# GritMaker.net
KiCad netlist of a schematic drawn in EasyEDA Pro
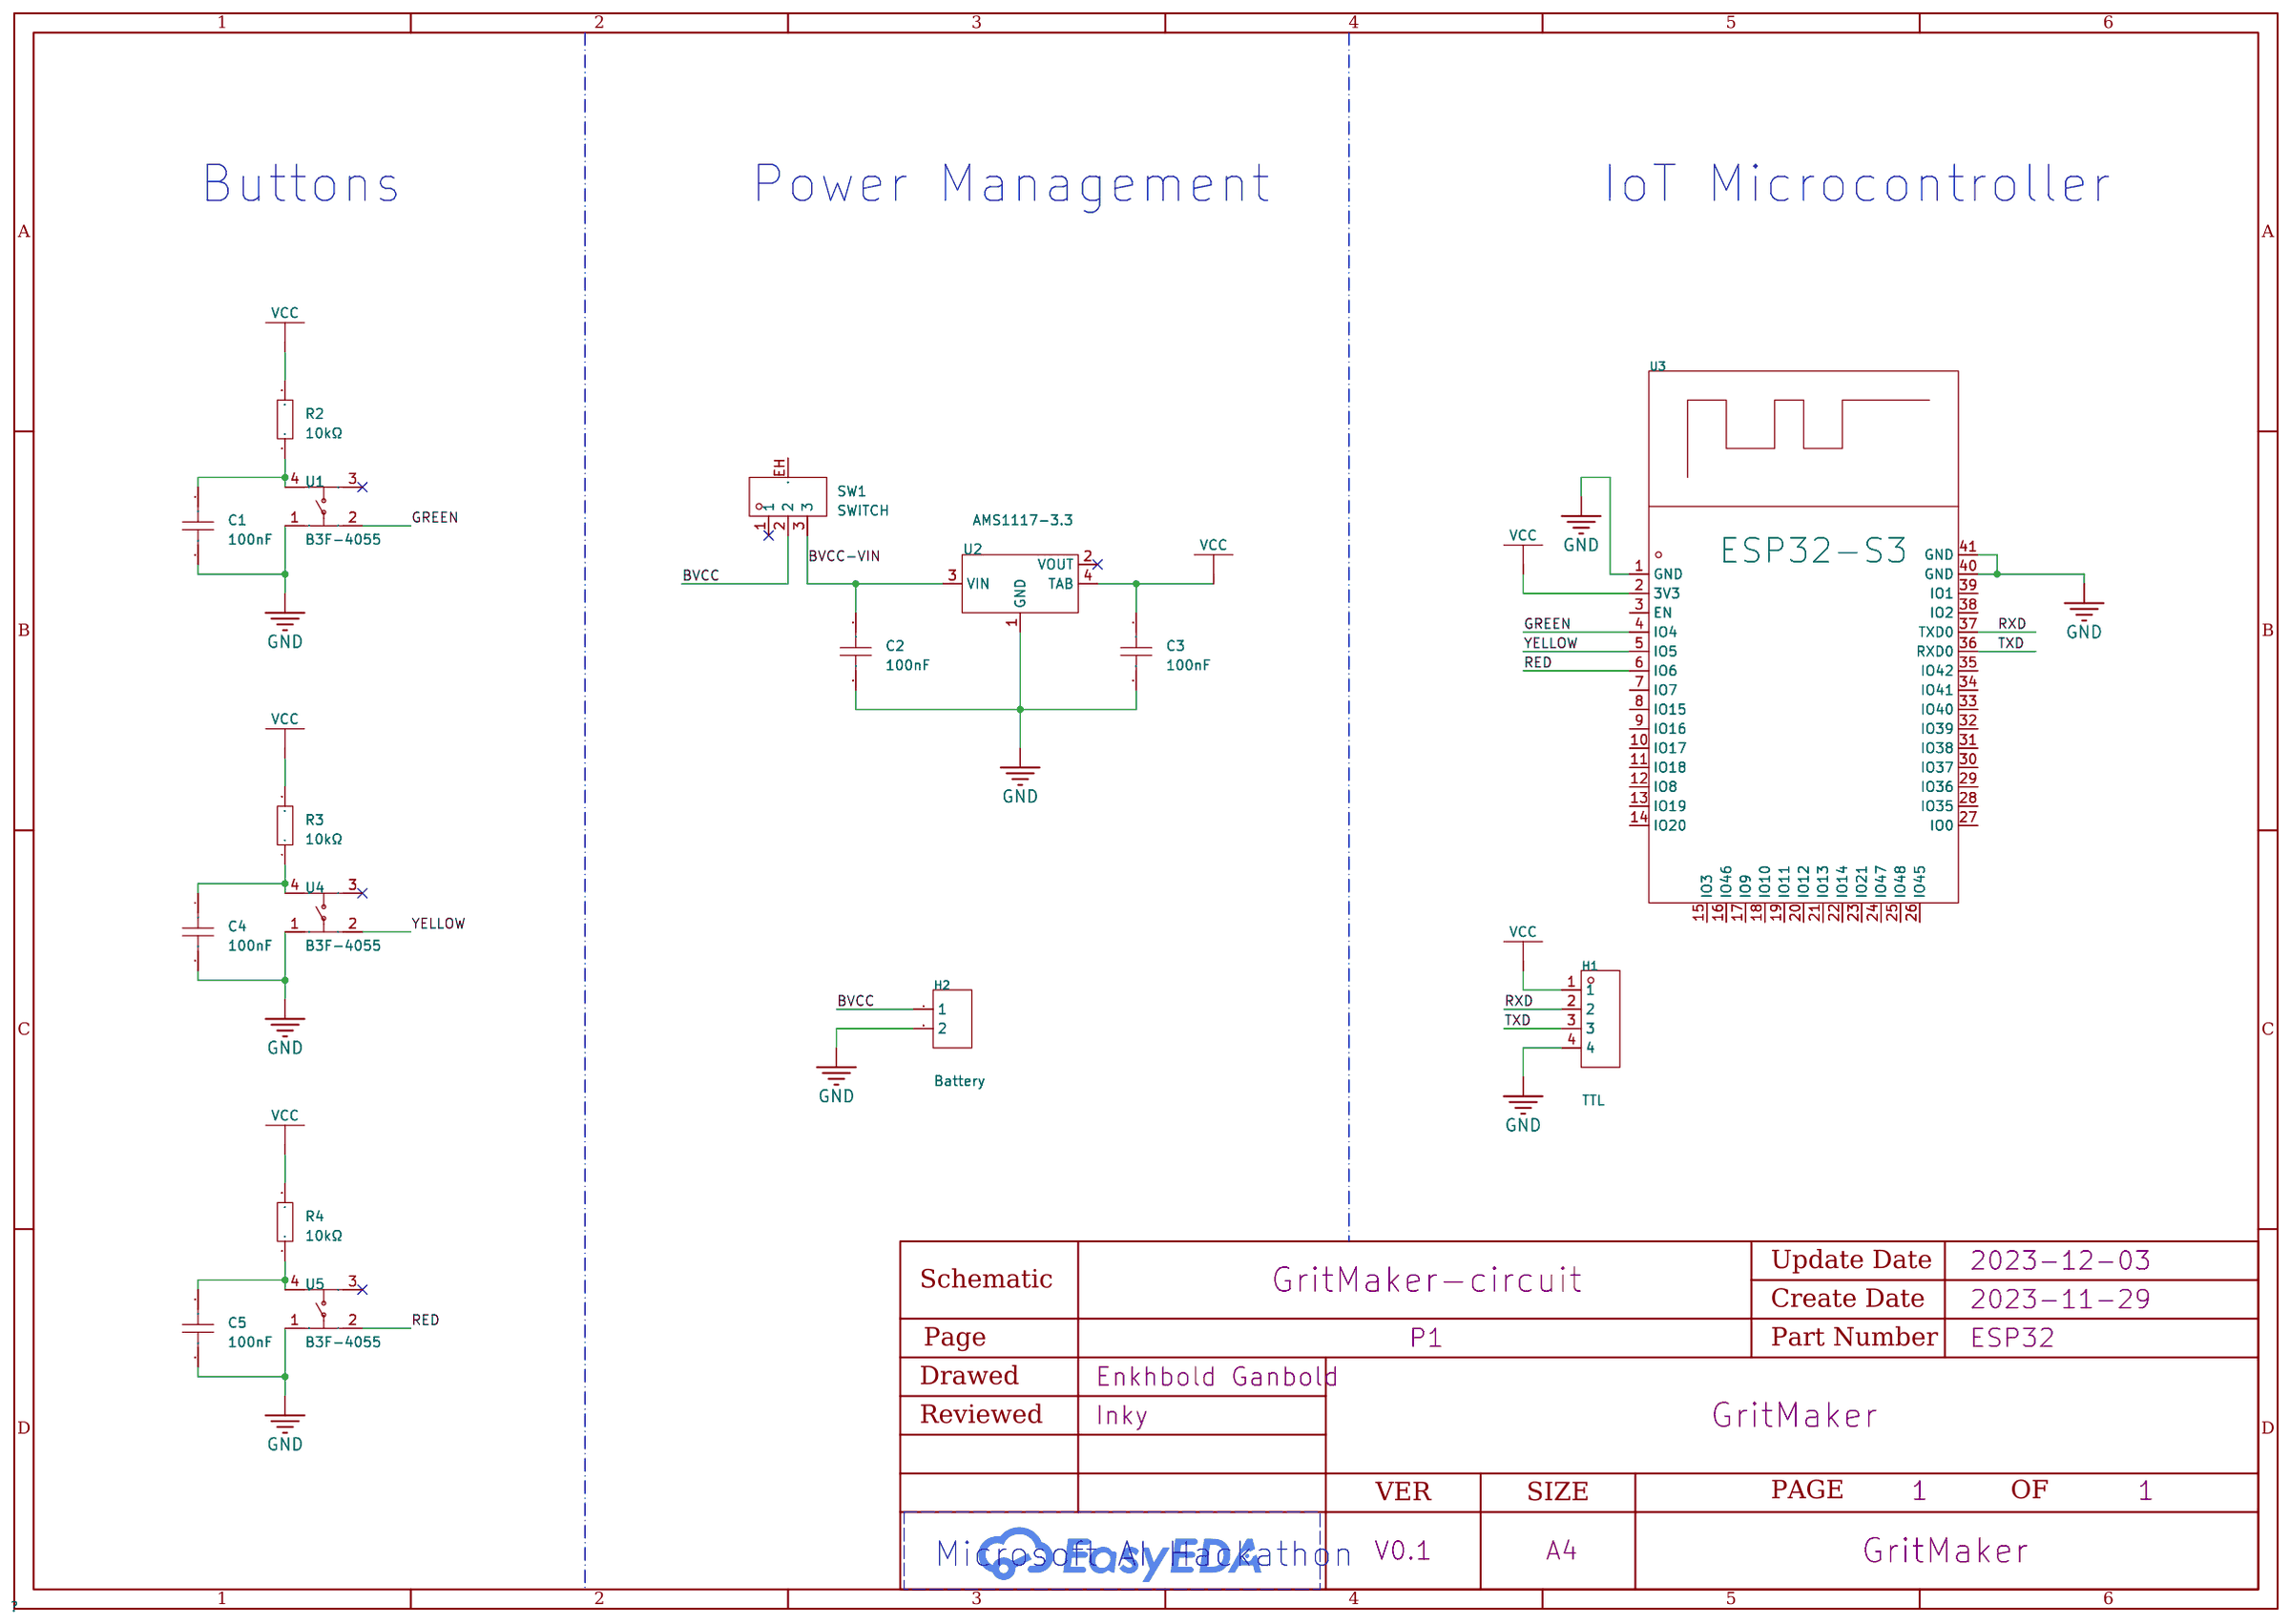
[diagram p0: schematic sheet]

(export (version "E")
  (design (tool "Eeschema 10.0.6"))
  (components
    (comp (ref "C1")
      (value "100nF")
      (footprint "easyedapro:C0201")
      (fields (field (name "Manufacturer Part") "178MU0002") (field (name "Manufacturer") "KNSCHA(科尼盛)"))
      (libsource (lib "easyedapro") (part "CAP"))
    )
    (comp (ref "C2")
      (value "100nF")
      (footprint "easyedapro:C0201")
      (fields (field (name "Manufacturer Part") "178MU0002") (field (name "Manufacturer") "KNSCHA(科尼盛)"))
      (libsource (lib "easyedapro") (part "CAP"))
    )
    (comp (ref "C3")
      (value "100nF")
      (footprint "easyedapro:C0201")
      (fields (field (name "Manufacturer Part") "178MU0002") (field (name "Manufacturer") "KNSCHA(科尼盛)"))
      (libsource (lib "easyedapro") (part "CAP"))
    )
    (comp (ref "C4")
      (value "100nF")
      (footprint "easyedapro:C0201")
      (fields (field (name "Manufacturer Part") "178MU0002") (field (name "Manufacturer") "KNSCHA(科尼盛)"))
      (libsource (lib "easyedapro") (part "CAP"))
    )
    (comp (ref "C5")
      (value "100nF")
      (footprint "easyedapro:C0201")
      (fields (field (name "Manufacturer Part") "178MU0002") (field (name "Manufacturer") "KNSCHA(科尼盛)"))
      (libsource (lib "easyedapro") (part "CAP"))
    )
    (comp (ref "H1")
      (value "TTL")
      (footprint "easyedapro:HDR-TH_4P-P2.54-V-M")
      (libsource (lib "easyedapro") (part "PZ254V-11-04P"))
    )
    (comp (ref "H2")
      (value "Battery")
      (footprint "easyedapro:HDR-TH_2P-P2.54-V-F")
      (libsource (lib "easyedapro") (part "Header-Female-2.54_1x2"))
    )
    (comp (ref "R2")
      (value "10kΩ")
      (footprint "easyedapro:R_AXIAL-0.4")
      (libsource (lib "easyedapro") (part "Res"))
    )
    (comp (ref "R3")
      (value "10kΩ")
      (footprint "easyedapro:R_AXIAL-0.4")
      (libsource (lib "easyedapro") (part "Res"))
    )
    (comp (ref "R4")
      (value "10kΩ")
      (footprint "easyedapro:R_AXIAL-0.4")
      (libsource (lib "easyedapro") (part "Res"))
    )
    (comp (ref "SW1")
      (value "SWITCH")
      (footprint "easyedapro:SW-TH_C9900003112")
      (libsource (lib "easyedapro") (part "SWITCH-拨动-三脚两档"))
    )
    (comp (ref "U1")
      (value "B3F-4055")
      (footprint "easyedapro:KEY-TH_4P-L6.0-W6.0-P4.50-LS6.5")
      (fields (field (name "Manufacturer") "OMRON(欧姆龙)"))
      (libsource (lib "easyedapro") (part "TC-1102-B-U-B"))
    )
    (comp (ref "U2")
      (value "AMS1117-3.3")
      (footprint "easyedapro:SOT-223_L6.7-W3.5-P2.30-BR")
      (description "Output Type:-")
      (fields (field (name "Manufacturer") "JSMSEMI(杰盛微)"))
      (libsource (lib "easyedapro") (part "AMS1117"))
    )
    (comp (ref "U3")
      (value "ESP32-S3")
      (footprint "easyedapro:WIRELM-SMD_ESP32-S3-WROOM-1")
      (fields
        (field (name "Manufacturer Part") "ESP32-S3-WROOM-1-N16")
        (field (name "Manufacturer") "ESPRESSIF(乐鑫)")
      )
      (libsource (lib "easyedapro") (part "ESP32-S3-WROOM-1(N16)"))
    )
    (comp (ref "U4")
      (value "B3F-4055")
      (footprint "easyedapro:KEY-TH_4P-L6.0-W6.0-P4.50-LS6.5")
      (fields (field (name "Manufacturer") "OMRON(欧姆龙)"))
      (libsource (lib "easyedapro") (part "TC-1102-B-U-B"))
    )
    (comp (ref "U5")
      (value "B3F-4055")
      (footprint "easyedapro:KEY-TH_4P-L6.0-W6.0-P4.50-LS6.5")
      (fields (field (name "Manufacturer") "OMRON(欧姆龙)"))
      (libsource (lib "easyedapro") (part "TC-1102-B-U-B"))
    )
  )
  (nets
    (net (code "1") (name "/BVCC") (class "Default")
      (node (ref "H2") (pin "1") (pinfunction "1_1") (pintype "input"))
      (node (ref "SW1") (pin "2") (pinfunction "2_2") (pintype "input"))
    )
    (net (code "2") (name "/BVCC-VIN") (class "Default")
      (node (ref "C2") (pin "1") (pinfunction "1_1") (pintype "input"))
      (node (ref "SW1") (pin "3") (pinfunction "3_3") (pintype "input"))
      (node (ref "U2") (pin "3") (pinfunction "VIN_3") (pintype "input"))
    )
    (net (code "3") (name "/GREEN") (class "Default")
      (node (ref "U1") (pin "2") (pinfunction "2_2") (pintype "input"))
      (node (ref "U3") (pin "4") (pinfunction "IO4_4") (pintype "input"))
    )
    (net (code "4") (name "/RED") (class "Default")
      (node (ref "U3") (pin "6") (pinfunction "IO6_6") (pintype "input"))
      (node (ref "U5") (pin "2") (pinfunction "2_2") (pintype "input"))
    )
    (net (code "5") (name "/RXD") (class "Default")
      (node (ref "H1") (pin "2") (pinfunction "2_2") (pintype "input"))
      (node (ref "U3") (pin "37") (pinfunction "TXD0_37") (pintype "input"))
    )
    (net (code "6") (name "/TXD") (class "Default")
      (node (ref "H1") (pin "3") (pinfunction "3_3") (pintype "input"))
      (node (ref "U3") (pin "36") (pinfunction "RXD0_36") (pintype "input"))
    )
    (net (code "7") (name "/YELLOW") (class "Default")
      (node (ref "U3") (pin "5") (pinfunction "IO5_5") (pintype "input"))
      (node (ref "U4") (pin "2") (pinfunction "2_2") (pintype "input"))
    )
    (net (code "8") (name "GND") (class "Default")
      (node (ref "C1") (pin "2") (pinfunction "2_2") (pintype "input"))
      (node (ref "C2") (pin "2") (pinfunction "2_2") (pintype "input"))
      (node (ref "C3") (pin "2") (pinfunction "2_2") (pintype "input"))
      (node (ref "C4") (pin "2") (pinfunction "2_2") (pintype "input"))
      (node (ref "C5") (pin "2") (pinfunction "2_2") (pintype "input"))
      (node (ref "H1") (pin "4") (pinfunction "4_4") (pintype "input"))
      (node (ref "H2") (pin "2") (pinfunction "2_2") (pintype "input"))
      (node (ref "U1") (pin "1") (pinfunction "1_1") (pintype "input"))
      (node (ref "U2") (pin "1") (pinfunction "GND_1") (pintype "input"))
      (node (ref "U3") (pin "1") (pinfunction "GND_1") (pintype "input"))
      (node (ref "U3") (pin "40") (pinfunction "GND_40") (pintype "input"))
      (node (ref "U3") (pin "41") (pinfunction "GND_41") (pintype "input"))
      (node (ref "U4") (pin "1") (pinfunction "1_1") (pintype "input"))
      (node (ref "U5") (pin "1") (pinfunction "1_1") (pintype "input"))
    )
    (net (code "9") (name "Net-(C1-Pad1)") (class "Default")
      (node (ref "C1") (pin "1") (pinfunction "1_1") (pintype "input"))
      (node (ref "R2") (pin "1") (pinfunction "1_1") (pintype "input"))
      (node (ref "U1") (pin "4") (pinfunction "4_4") (pintype "input"))
    )
    (net (code "10") (name "Net-(C4-Pad1)") (class "Default")
      (node (ref "C4") (pin "1") (pinfunction "1_1") (pintype "input"))
      (node (ref "R3") (pin "1") (pinfunction "1_1") (pintype "input"))
      (node (ref "U4") (pin "4") (pinfunction "4_4") (pintype "input"))
    )
    (net (code "11") (name "Net-(C5-Pad1)") (class "Default")
      (node (ref "C5") (pin "1") (pinfunction "1_1") (pintype "input"))
      (node (ref "R4") (pin "1") (pinfunction "1_1") (pintype "input"))
      (node (ref "U5") (pin "4") (pinfunction "4_4") (pintype "input"))
    )
    (net (code "12") (name "VCC") (class "Default")
      (node (ref "C3") (pin "1") (pinfunction "1_1") (pintype "input"))
      (node (ref "H1") (pin "1") (pinfunction "1_1") (pintype "input"))
      (node (ref "R2") (pin "2") (pinfunction "2_2") (pintype "input"))
      (node (ref "R3") (pin "2") (pinfunction "2_2") (pintype "input"))
      (node (ref "R4") (pin "2") (pinfunction "2_2") (pintype "input"))
      (node (ref "U2") (pin "4") (pinfunction "TAB_4") (pintype "input"))
      (node (ref "U3") (pin "2") (pinfunction "3V3_2") (pintype "input"))
    )
    (net (code "13") (name "unconnected-(SW1-Pad1)") (class "Default")
      (node (ref "SW1") (pin "1") (pinfunction "1_1") (pintype "input+no_connect"))
    )
    (net (code "14") (name "unconnected-(SW1-PadEH)") (class "Default")
      (node (ref "SW1") (pin "EH") (pinfunction "EH_EH") (pintype "input"))
    )
    (net (code "15") (name "unconnected-(U1-Pad3)") (class "Default")
      (node (ref "U1") (pin "3") (pinfunction "3_3") (pintype "input+no_connect"))
    )
    (net (code "16") (name "unconnected-(U2-VOUT-Pad2)") (class "Default")
      (node (ref "U2") (pin "2") (pinfunction "VOUT_2") (pintype "input+no_connect"))
    )
    (net (code "17") (name "unconnected-(U3-EN-Pad3)") (class "Default")
      (node (ref "U3") (pin "3") (pinfunction "EN_3") (pintype "input"))
    )
    (net (code "18") (name "unconnected-(U3-IO0-Pad27)") (class "Default")
      (node (ref "U3") (pin "27") (pinfunction "IO0_27") (pintype "input"))
    )
    (net (code "19") (name "unconnected-(U3-IO1-Pad39)") (class "Default")
      (node (ref "U3") (pin "39") (pinfunction "IO1_39") (pintype "input"))
    )
    (net (code "20") (name "unconnected-(U3-IO2-Pad38)") (class "Default")
      (node (ref "U3") (pin "38") (pinfunction "IO2_38") (pintype "input"))
    )
    (net (code "21") (name "unconnected-(U3-IO3-Pad15)") (class "Default")
      (node (ref "U3") (pin "15") (pinfunction "IO3_15") (pintype "input"))
    )
    (net (code "22") (name "unconnected-(U3-IO7-Pad7)") (class "Default")
      (node (ref "U3") (pin "7") (pinfunction "IO7_7") (pintype "input"))
    )
    (net (code "23") (name "unconnected-(U3-IO8-Pad12)") (class "Default")
      (node (ref "U3") (pin "12") (pinfunction "IO8_12") (pintype "input"))
    )
    (net (code "24") (name "unconnected-(U3-IO9-Pad17)") (class "Default")
      (node (ref "U3") (pin "17") (pinfunction "IO9_17") (pintype "input"))
    )
    (net (code "25") (name "unconnected-(U3-IO10-Pad18)") (class "Default")
      (node (ref "U3") (pin "18") (pinfunction "IO10_18") (pintype "input"))
    )
    (net (code "26") (name "unconnected-(U3-IO11-Pad19)") (class "Default")
      (node (ref "U3") (pin "19") (pinfunction "IO11_19") (pintype "input"))
    )
    (net (code "27") (name "unconnected-(U3-IO12-Pad20)") (class "Default")
      (node (ref "U3") (pin "20") (pinfunction "IO12_20") (pintype "input"))
    )
    (net (code "28") (name "unconnected-(U3-IO13-Pad21)") (class "Default")
      (node (ref "U3") (pin "21") (pinfunction "IO13_21") (pintype "input"))
    )
    (net (code "29") (name "unconnected-(U3-IO14-Pad22)") (class "Default")
      (node (ref "U3") (pin "22") (pinfunction "IO14_22") (pintype "input"))
    )
    (net (code "30") (name "unconnected-(U3-IO15-Pad8)") (class "Default")
      (node (ref "U3") (pin "8") (pinfunction "IO15_8") (pintype "input"))
    )
    (net (code "31") (name "unconnected-(U3-IO16-Pad9)") (class "Default")
      (node (ref "U3") (pin "9") (pinfunction "IO16_9") (pintype "input"))
    )
    (net (code "32") (name "unconnected-(U3-IO17-Pad10)") (class "Default")
      (node (ref "U3") (pin "10") (pinfunction "IO17_10") (pintype "input"))
    )
    (net (code "33") (name "unconnected-(U3-IO18-Pad11)") (class "Default")
      (node (ref "U3") (pin "11") (pinfunction "IO18_11") (pintype "input"))
    )
    (net (code "34") (name "unconnected-(U3-IO19-Pad13)") (class "Default")
      (node (ref "U3") (pin "13") (pinfunction "IO19_13") (pintype "input"))
    )
    (net (code "35") (name "unconnected-(U3-IO20-Pad14)") (class "Default")
      (node (ref "U3") (pin "14") (pinfunction "IO20_14") (pintype "input"))
    )
    (net (code "36") (name "unconnected-(U3-IO21-Pad23)") (class "Default")
      (node (ref "U3") (pin "23") (pinfunction "IO21_23") (pintype "input"))
    )
    (net (code "37") (name "unconnected-(U3-IO35-Pad28)") (class "Default")
      (node (ref "U3") (pin "28") (pinfunction "IO35_28") (pintype "input"))
    )
    (net (code "38") (name "unconnected-(U3-IO36-Pad29)") (class "Default")
      (node (ref "U3") (pin "29") (pinfunction "IO36_29") (pintype "input"))
    )
    (net (code "39") (name "unconnected-(U3-IO37-Pad30)") (class "Default")
      (node (ref "U3") (pin "30") (pinfunction "IO37_30") (pintype "input"))
    )
    (net (code "40") (name "unconnected-(U3-IO38-Pad31)") (class "Default")
      (node (ref "U3") (pin "31") (pinfunction "IO38_31") (pintype "input"))
    )
    (net (code "41") (name "unconnected-(U3-IO39-Pad32)") (class "Default")
      (node (ref "U3") (pin "32") (pinfunction "IO39_32") (pintype "input"))
    )
    (net (code "42") (name "unconnected-(U3-IO40-Pad33)") (class "Default")
      (node (ref "U3") (pin "33") (pinfunction "IO40_33") (pintype "input"))
    )
    (net (code "43") (name "unconnected-(U3-IO41-Pad34)") (class "Default")
      (node (ref "U3") (pin "34") (pinfunction "IO41_34") (pintype "input"))
    )
    (net (code "44") (name "unconnected-(U3-IO42-Pad35)") (class "Default")
      (node (ref "U3") (pin "35") (pinfunction "IO42_35") (pintype "input"))
    )
    (net (code "45") (name "unconnected-(U3-IO45-Pad26)") (class "Default")
      (node (ref "U3") (pin "26") (pinfunction "IO45_26") (pintype "input"))
    )
    (net (code "46") (name "unconnected-(U3-IO46-Pad16)") (class "Default")
      (node (ref "U3") (pin "16") (pinfunction "IO46_16") (pintype "input"))
    )
    (net (code "47") (name "unconnected-(U3-IO47-Pad24)") (class "Default")
      (node (ref "U3") (pin "24") (pinfunction "IO47_24") (pintype "input"))
    )
    (net (code "48") (name "unconnected-(U3-IO48-Pad25)") (class "Default")
      (node (ref "U3") (pin "25") (pinfunction "IO48_25") (pintype "input"))
    )
    (net (code "49") (name "unconnected-(U4-Pad3)") (class "Default")
      (node (ref "U4") (pin "3") (pinfunction "3_3") (pintype "input+no_connect"))
    )
    (net (code "50") (name "unconnected-(U5-Pad3)") (class "Default")
      (node (ref "U5") (pin "3") (pinfunction "3_3") (pintype "input+no_connect"))
    )
  )
)
